# lcd.net
KiCad netlist of a schematic drawn in Altium Designer
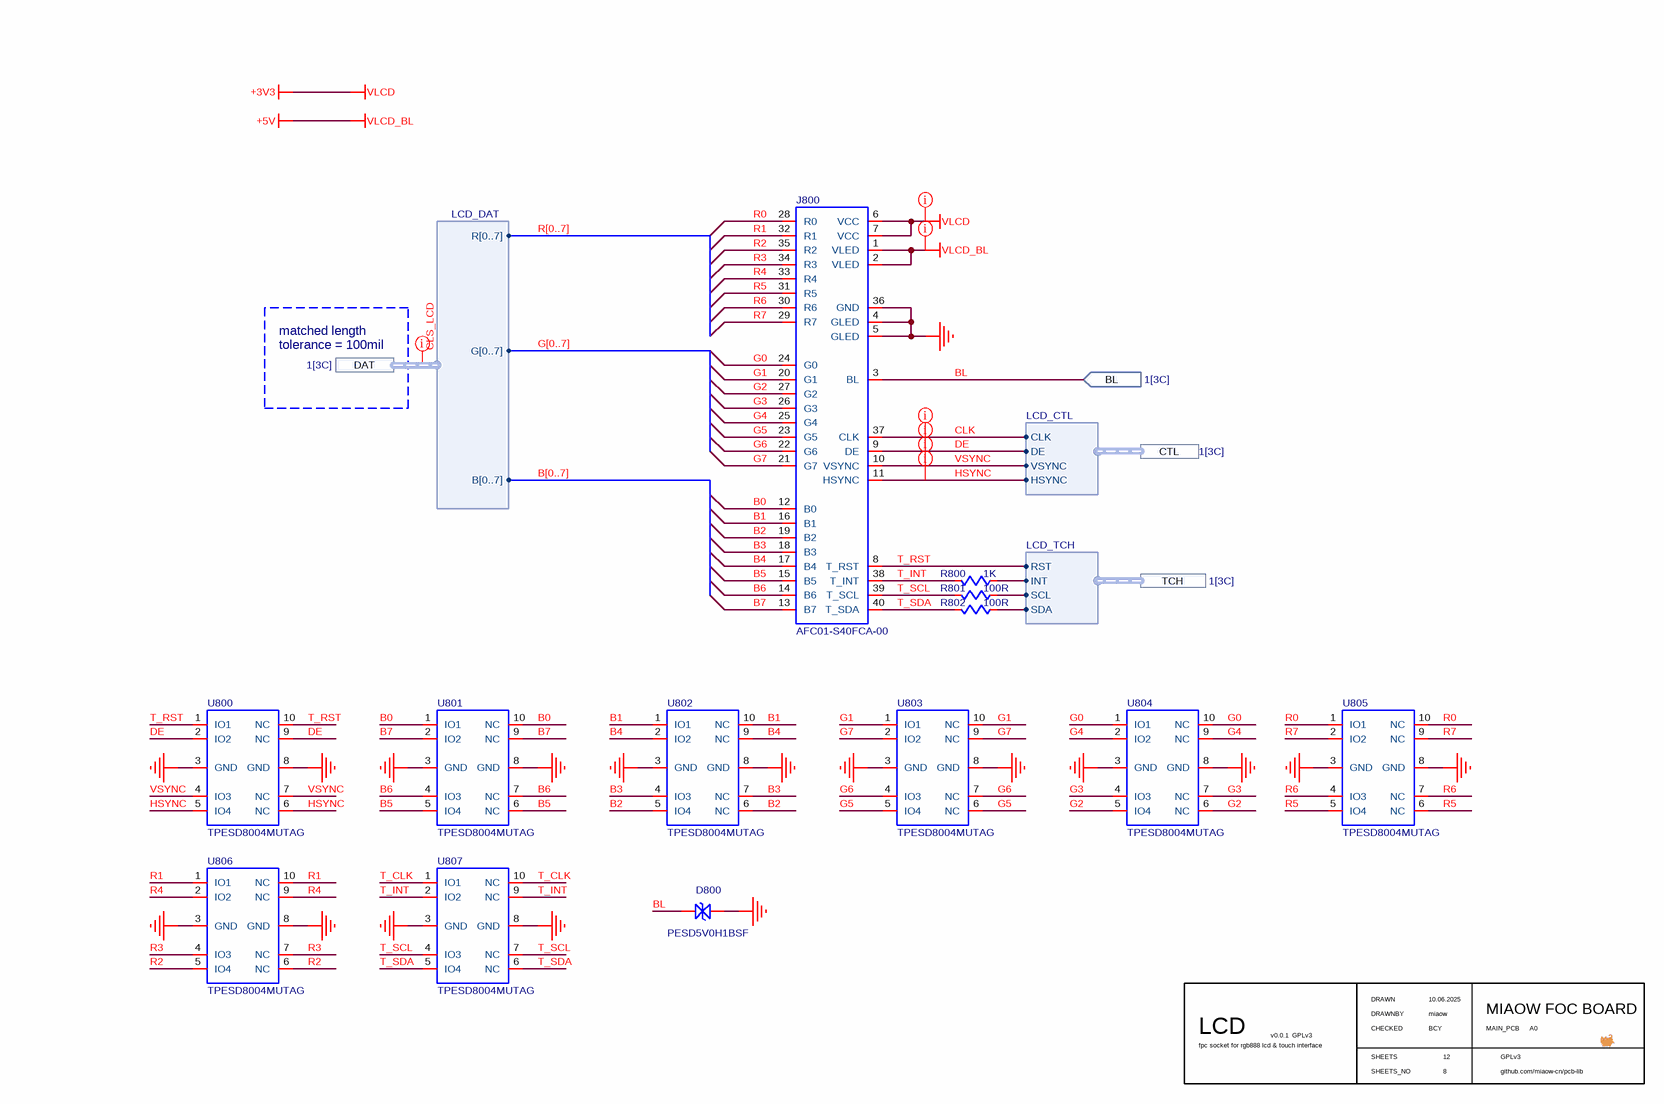
[diagram p0: lcd.SchDoc]

(export (version "E")
  (design (tool "Eeschema 10.0.6"))
  (components
    (comp (ref "D800")
      (value "PESD5V0H1BSF")
      (footprint "mw:PESD5V0H1BSF")
      (description "TVS/ESD")
      (libsource (lib "mw") (part "PESD5V0H1BSF"))
    )
    (comp (ref "J800")
      (value "AFC01-S40FCA-00")
      (footprint "mw:AFC01-S40FCA-00")
      (libsource (lib "mw") (part "FPC-RGBLCD"))
    )
    (comp (ref "R800")
      (value "1K")
      (footprint "mw:R0402")
      (fields (field (name "Comment") "R"))
      (libsource (lib "mw") (part "R"))
    )
    (comp (ref "R801")
      (value "100R")
      (footprint "mw:R0402")
      (fields (field (name "Comment") "R"))
      (libsource (lib "mw") (part "R"))
    )
    (comp (ref "R802")
      (value "100R")
      (footprint "mw:R0402")
      (fields (field (name "Comment") "R"))
      (libsource (lib "mw") (part "R"))
    )
    (comp (ref "U800")
      (value "TPESD8004MUTAG")
      (footprint "mw:TPESD8004MUTAG")
      (description "TVS/ESD")
      (libsource (lib "mw") (part "TPESD8004MUTAG"))
    )
    (comp (ref "U801")
      (value "TPESD8004MUTAG")
      (footprint "mw:TPESD8004MUTAG")
      (description "TVS/ESD")
      (libsource (lib "mw") (part "TPESD8004MUTAG"))
    )
    (comp (ref "U802")
      (value "TPESD8004MUTAG")
      (footprint "mw:TPESD8004MUTAG")
      (description "TVS/ESD")
      (libsource (lib "mw") (part "TPESD8004MUTAG"))
    )
    (comp (ref "U803")
      (value "TPESD8004MUTAG")
      (footprint "mw:TPESD8004MUTAG")
      (description "TVS/ESD")
      (libsource (lib "mw") (part "TPESD8004MUTAG"))
    )
    (comp (ref "U804")
      (value "TPESD8004MUTAG")
      (footprint "mw:TPESD8004MUTAG")
      (description "TVS/ESD")
      (libsource (lib "mw") (part "TPESD8004MUTAG"))
    )
    (comp (ref "U805")
      (value "TPESD8004MUTAG")
      (footprint "mw:TPESD8004MUTAG")
      (description "TVS/ESD")
      (libsource (lib "mw") (part "TPESD8004MUTAG"))
    )
    (comp (ref "U806")
      (value "TPESD8004MUTAG")
      (footprint "mw:TPESD8004MUTAG")
      (description "TVS/ESD")
      (libsource (lib "mw") (part "TPESD8004MUTAG"))
    )
    (comp (ref "U807")
      (value "TPESD8004MUTAG")
      (footprint "mw:TPESD8004MUTAG")
      (description "TVS/ESD")
      (libsource (lib "mw") (part "TPESD8004MUTAG"))
    )
  )
  (nets
    (net (code "4") (name "+3V3") (class "Default")
      (node (ref "J800") (pin "6") (pinfunction "VCC_6") (pintype "passive"))
      (node (ref "J800") (pin "7") (pinfunction "VCC_7") (pintype "passive"))
    )
    (net (code "5") (name "+5V") (class "Default")
      (node (ref "J800") (pin "1") (pinfunction "VLED_1") (pintype "passive"))
      (node (ref "J800") (pin "2") (pinfunction "VLED_2") (pintype "passive"))
    )
    (net (code "6") (name "/B0") (class "Default")
      (node (ref "J800") (pin "12") (pinfunction "B0_12") (pintype "passive"))
      (node (ref "U801") (pin "1") (pinfunction "IO1_1") (pintype "passive"))
      (node (ref "U801") (pin "10") (pinfunction "NC_10") (pintype "passive"))
    )
    (net (code "7") (name "/B1") (class "Default")
      (node (ref "J800") (pin "16") (pinfunction "B1_16") (pintype "passive"))
      (node (ref "U802") (pin "1") (pinfunction "IO1_1") (pintype "passive"))
      (node (ref "U802") (pin "10") (pinfunction "NC_10") (pintype "passive"))
    )
    (net (code "8") (name "/B2") (class "Default")
      (node (ref "J800") (pin "19") (pinfunction "B2_19") (pintype "passive"))
      (node (ref "U802") (pin "5") (pinfunction "IO4_5") (pintype "passive"))
      (node (ref "U802") (pin "6") (pinfunction "NC_6") (pintype "passive"))
    )
    (net (code "9") (name "/B3") (class "Default")
      (node (ref "J800") (pin "18") (pinfunction "B3_18") (pintype "passive"))
      (node (ref "U802") (pin "4") (pinfunction "IO3_4") (pintype "passive"))
      (node (ref "U802") (pin "7") (pinfunction "NC_7") (pintype "passive"))
    )
    (net (code "10") (name "/B4") (class "Default")
      (node (ref "J800") (pin "17") (pinfunction "B4_17") (pintype "passive"))
      (node (ref "U802") (pin "2") (pinfunction "IO2_2") (pintype "passive"))
      (node (ref "U802") (pin "9") (pinfunction "NC_9") (pintype "passive"))
    )
    (net (code "11") (name "/B5") (class "Default")
      (node (ref "J800") (pin "15") (pinfunction "B5_15") (pintype "passive"))
      (node (ref "U801") (pin "5") (pinfunction "IO4_5") (pintype "passive"))
      (node (ref "U801") (pin "6") (pinfunction "NC_6") (pintype "passive"))
    )
    (net (code "12") (name "/B6") (class "Default")
      (node (ref "J800") (pin "14") (pinfunction "B6_14") (pintype "passive"))
      (node (ref "U801") (pin "4") (pinfunction "IO3_4") (pintype "passive"))
      (node (ref "U801") (pin "7") (pinfunction "NC_7") (pintype "passive"))
    )
    (net (code "13") (name "/B7") (class "Default")
      (node (ref "J800") (pin "13") (pinfunction "B7_13") (pintype "passive"))
      (node (ref "U801") (pin "2") (pinfunction "IO2_2") (pintype "passive"))
      (node (ref "U801") (pin "9") (pinfunction "NC_9") (pintype "passive"))
    )
    (net (code "14") (name "/BL") (class "Default")
      (node (ref "D800") (pin "1") (pinfunction "1_1") (pintype "passive"))
      (node (ref "J800") (pin "3") (pinfunction "BL_3") (pintype "passive"))
    )
    (net (code "16") (name "/CLK") (class "Default")
      (node (ref "J800") (pin "37") (pinfunction "CLK_37") (pintype "passive"))
    )
    (net (code "18") (name "/DE") (class "Default")
      (node (ref "J800") (pin "9") (pinfunction "DE_9") (pintype "passive"))
      (node (ref "U800") (pin "2") (pinfunction "IO2_2") (pintype "passive"))
      (node (ref "U800") (pin "9") (pinfunction "NC_9") (pintype "passive"))
    )
    (net (code "19") (name "/G0") (class "Default")
      (node (ref "J800") (pin "24") (pinfunction "G0_24") (pintype "passive"))
      (node (ref "U804") (pin "1") (pinfunction "IO1_1") (pintype "passive"))
      (node (ref "U804") (pin "10") (pinfunction "NC_10") (pintype "passive"))
    )
    (net (code "20") (name "/G1") (class "Default")
      (node (ref "J800") (pin "20") (pinfunction "G1_20") (pintype "passive"))
      (node (ref "U803") (pin "1") (pinfunction "IO1_1") (pintype "passive"))
      (node (ref "U803") (pin "10") (pinfunction "NC_10") (pintype "passive"))
    )
    (net (code "21") (name "/G2") (class "Default")
      (node (ref "J800") (pin "27") (pinfunction "G2_27") (pintype "passive"))
      (node (ref "U804") (pin "5") (pinfunction "IO4_5") (pintype "passive"))
      (node (ref "U804") (pin "6") (pinfunction "NC_6") (pintype "passive"))
    )
    (net (code "22") (name "/G3") (class "Default")
      (node (ref "J800") (pin "26") (pinfunction "G3_26") (pintype "passive"))
      (node (ref "U804") (pin "4") (pinfunction "IO3_4") (pintype "passive"))
      (node (ref "U804") (pin "7") (pinfunction "NC_7") (pintype "passive"))
    )
    (net (code "23") (name "/G4") (class "Default")
      (node (ref "J800") (pin "25") (pinfunction "G4_25") (pintype "passive"))
      (node (ref "U804") (pin "2") (pinfunction "IO2_2") (pintype "passive"))
      (node (ref "U804") (pin "9") (pinfunction "NC_9") (pintype "passive"))
    )
    (net (code "24") (name "/G5") (class "Default")
      (node (ref "J800") (pin "23") (pinfunction "G5_23") (pintype "passive"))
      (node (ref "U803") (pin "5") (pinfunction "IO4_5") (pintype "passive"))
      (node (ref "U803") (pin "6") (pinfunction "NC_6") (pintype "passive"))
    )
    (net (code "25") (name "/G6") (class "Default")
      (node (ref "J800") (pin "22") (pinfunction "G6_22") (pintype "passive"))
      (node (ref "U803") (pin "4") (pinfunction "IO3_4") (pintype "passive"))
      (node (ref "U803") (pin "7") (pinfunction "NC_7") (pintype "passive"))
    )
    (net (code "26") (name "/G7") (class "Default")
      (node (ref "J800") (pin "21") (pinfunction "G7_21") (pintype "passive"))
      (node (ref "U803") (pin "2") (pinfunction "IO2_2") (pintype "passive"))
      (node (ref "U803") (pin "9") (pinfunction "NC_9") (pintype "passive"))
    )
    (net (code "28") (name "/HSYNC") (class "Default")
      (node (ref "J800") (pin "11") (pinfunction "HSYNC_11") (pintype "passive"))
      (node (ref "U800") (pin "5") (pinfunction "IO4_5") (pintype "passive"))
      (node (ref "U800") (pin "6") (pinfunction "NC_6") (pintype "passive"))
    )
    (net (code "29") (name "/INT") (class "Default")
      (node (ref "R800") (pin "2") (pinfunction "2_2") (pintype "passive"))
    )
    (net (code "30") (name "/R0") (class "Default")
      (node (ref "J800") (pin "28") (pinfunction "R0_28") (pintype "passive"))
      (node (ref "U805") (pin "1") (pinfunction "IO1_1") (pintype "passive"))
      (node (ref "U805") (pin "10") (pinfunction "NC_10") (pintype "passive"))
    )
    (net (code "31") (name "/R1") (class "Default")
      (node (ref "J800") (pin "32") (pinfunction "R1_32") (pintype "passive"))
      (node (ref "U806") (pin "1") (pinfunction "IO1_1") (pintype "passive"))
      (node (ref "U806") (pin "10") (pinfunction "NC_10") (pintype "passive"))
    )
    (net (code "32") (name "/R2") (class "Default")
      (node (ref "J800") (pin "35") (pinfunction "R2_35") (pintype "passive"))
      (node (ref "U806") (pin "5") (pinfunction "IO4_5") (pintype "passive"))
      (node (ref "U806") (pin "6") (pinfunction "NC_6") (pintype "passive"))
    )
    (net (code "33") (name "/R3") (class "Default")
      (node (ref "J800") (pin "34") (pinfunction "R3_34") (pintype "passive"))
      (node (ref "U806") (pin "4") (pinfunction "IO3_4") (pintype "passive"))
      (node (ref "U806") (pin "7") (pinfunction "NC_7") (pintype "passive"))
    )
    (net (code "34") (name "/R4") (class "Default")
      (node (ref "J800") (pin "33") (pinfunction "R4_33") (pintype "passive"))
      (node (ref "U806") (pin "2") (pinfunction "IO2_2") (pintype "passive"))
      (node (ref "U806") (pin "9") (pinfunction "NC_9") (pintype "passive"))
    )
    (net (code "35") (name "/R5") (class "Default")
      (node (ref "J800") (pin "31") (pinfunction "R5_31") (pintype "passive"))
      (node (ref "U805") (pin "5") (pinfunction "IO4_5") (pintype "passive"))
      (node (ref "U805") (pin "6") (pinfunction "NC_6") (pintype "passive"))
    )
    (net (code "36") (name "/R6") (class "Default")
      (node (ref "J800") (pin "30") (pinfunction "R6_30") (pintype "passive"))
      (node (ref "U805") (pin "4") (pinfunction "IO3_4") (pintype "passive"))
      (node (ref "U805") (pin "7") (pinfunction "NC_7") (pintype "passive"))
    )
    (net (code "37") (name "/R7") (class "Default")
      (node (ref "J800") (pin "29") (pinfunction "R7_29") (pintype "passive"))
      (node (ref "U805") (pin "2") (pinfunction "IO2_2") (pintype "passive"))
      (node (ref "U805") (pin "9") (pinfunction "NC_9") (pintype "passive"))
    )
    (net (code "38") (name "/SCL") (class "Default")
      (node (ref "R801") (pin "2") (pinfunction "2_2") (pintype "passive"))
    )
    (net (code "39") (name "/SDA") (class "Default")
      (node (ref "R802") (pin "2") (pinfunction "2_2") (pintype "passive"))
    )
    (net (code "40") (name "/T_CLK") (class "Default")
      (node (ref "U807") (pin "1") (pinfunction "IO1_1") (pintype "passive"))
      (node (ref "U807") (pin "10") (pinfunction "NC_10") (pintype "passive"))
    )
    (net (code "41") (name "/T_INT") (class "Default")
      (node (ref "J800") (pin "38") (pinfunction "T_INT_38") (pintype "passive"))
      (node (ref "R800") (pin "1") (pinfunction "1_1") (pintype "passive"))
      (node (ref "U807") (pin "2") (pinfunction "IO2_2") (pintype "passive"))
      (node (ref "U807") (pin "9") (pinfunction "NC_9") (pintype "passive"))
    )
    (net (code "42") (name "/T_RST") (class "Default")
      (node (ref "J800") (pin "8") (pinfunction "T_RST_8") (pintype "passive"))
      (node (ref "U800") (pin "1") (pinfunction "IO1_1") (pintype "passive"))
      (node (ref "U800") (pin "10") (pinfunction "NC_10") (pintype "passive"))
    )
    (net (code "43") (name "/T_SCL") (class "Default")
      (node (ref "J800") (pin "39") (pinfunction "T_SCL_39") (pintype "passive"))
      (node (ref "R801") (pin "1") (pinfunction "1_1") (pintype "passive"))
      (node (ref "U807") (pin "4") (pinfunction "IO3_4") (pintype "passive"))
      (node (ref "U807") (pin "7") (pinfunction "NC_7") (pintype "passive"))
    )
    (net (code "44") (name "/T_SDA") (class "Default")
      (node (ref "J800") (pin "40") (pinfunction "T_SDA_40") (pintype "passive"))
      (node (ref "R802") (pin "1") (pinfunction "1_1") (pintype "passive"))
      (node (ref "U807") (pin "5") (pinfunction "IO4_5") (pintype "passive"))
      (node (ref "U807") (pin "6") (pinfunction "NC_6") (pintype "passive"))
    )
    (net (code "45") (name "/VSYNC") (class "Default")
      (node (ref "J800") (pin "10") (pinfunction "VSYNC_10") (pintype "passive"))
      (node (ref "U800") (pin "4") (pinfunction "IO3_4") (pintype "passive"))
      (node (ref "U800") (pin "7") (pinfunction "NC_7") (pintype "passive"))
    )
    (net (code "49") (name "GND") (class "Default")
      (node (ref "D800") (pin "2") (pinfunction "2_2") (pintype "passive"))
      (node (ref "J800") (pin "36") (pinfunction "GND_36") (pintype "passive"))
      (node (ref "J800") (pin "4") (pinfunction "GLED_4") (pintype "passive"))
      (node (ref "J800") (pin "5") (pinfunction "GLED_5") (pintype "passive"))
      (node (ref "U800") (pin "3") (pinfunction "GND_3") (pintype "passive"))
      (node (ref "U800") (pin "8") (pinfunction "GND_8") (pintype "passive"))
      (node (ref "U801") (pin "3") (pinfunction "GND_3") (pintype "passive"))
      (node (ref "U801") (pin "8") (pinfunction "GND_8") (pintype "passive"))
      (node (ref "U802") (pin "3") (pinfunction "GND_3") (pintype "passive"))
      (node (ref "U802") (pin "8") (pinfunction "GND_8") (pintype "passive"))
      (node (ref "U803") (pin "3") (pinfunction "GND_3") (pintype "passive"))
      (node (ref "U803") (pin "8") (pinfunction "GND_8") (pintype "passive"))
      (node (ref "U804") (pin "3") (pinfunction "GND_3") (pintype "passive"))
      (node (ref "U804") (pin "8") (pinfunction "GND_8") (pintype "passive"))
      (node (ref "U805") (pin "3") (pinfunction "GND_3") (pintype "passive"))
      (node (ref "U805") (pin "8") (pinfunction "GND_8") (pintype "passive"))
      (node (ref "U806") (pin "3") (pinfunction "GND_3") (pintype "passive"))
      (node (ref "U806") (pin "8") (pinfunction "GND_8") (pintype "passive"))
      (node (ref "U807") (pin "3") (pinfunction "GND_3") (pintype "passive"))
      (node (ref "U807") (pin "8") (pinfunction "GND_8") (pintype "passive"))
    )
  )
)
